# bs_prod.net
KiCad netlist of a schematic drawn in EAGLE
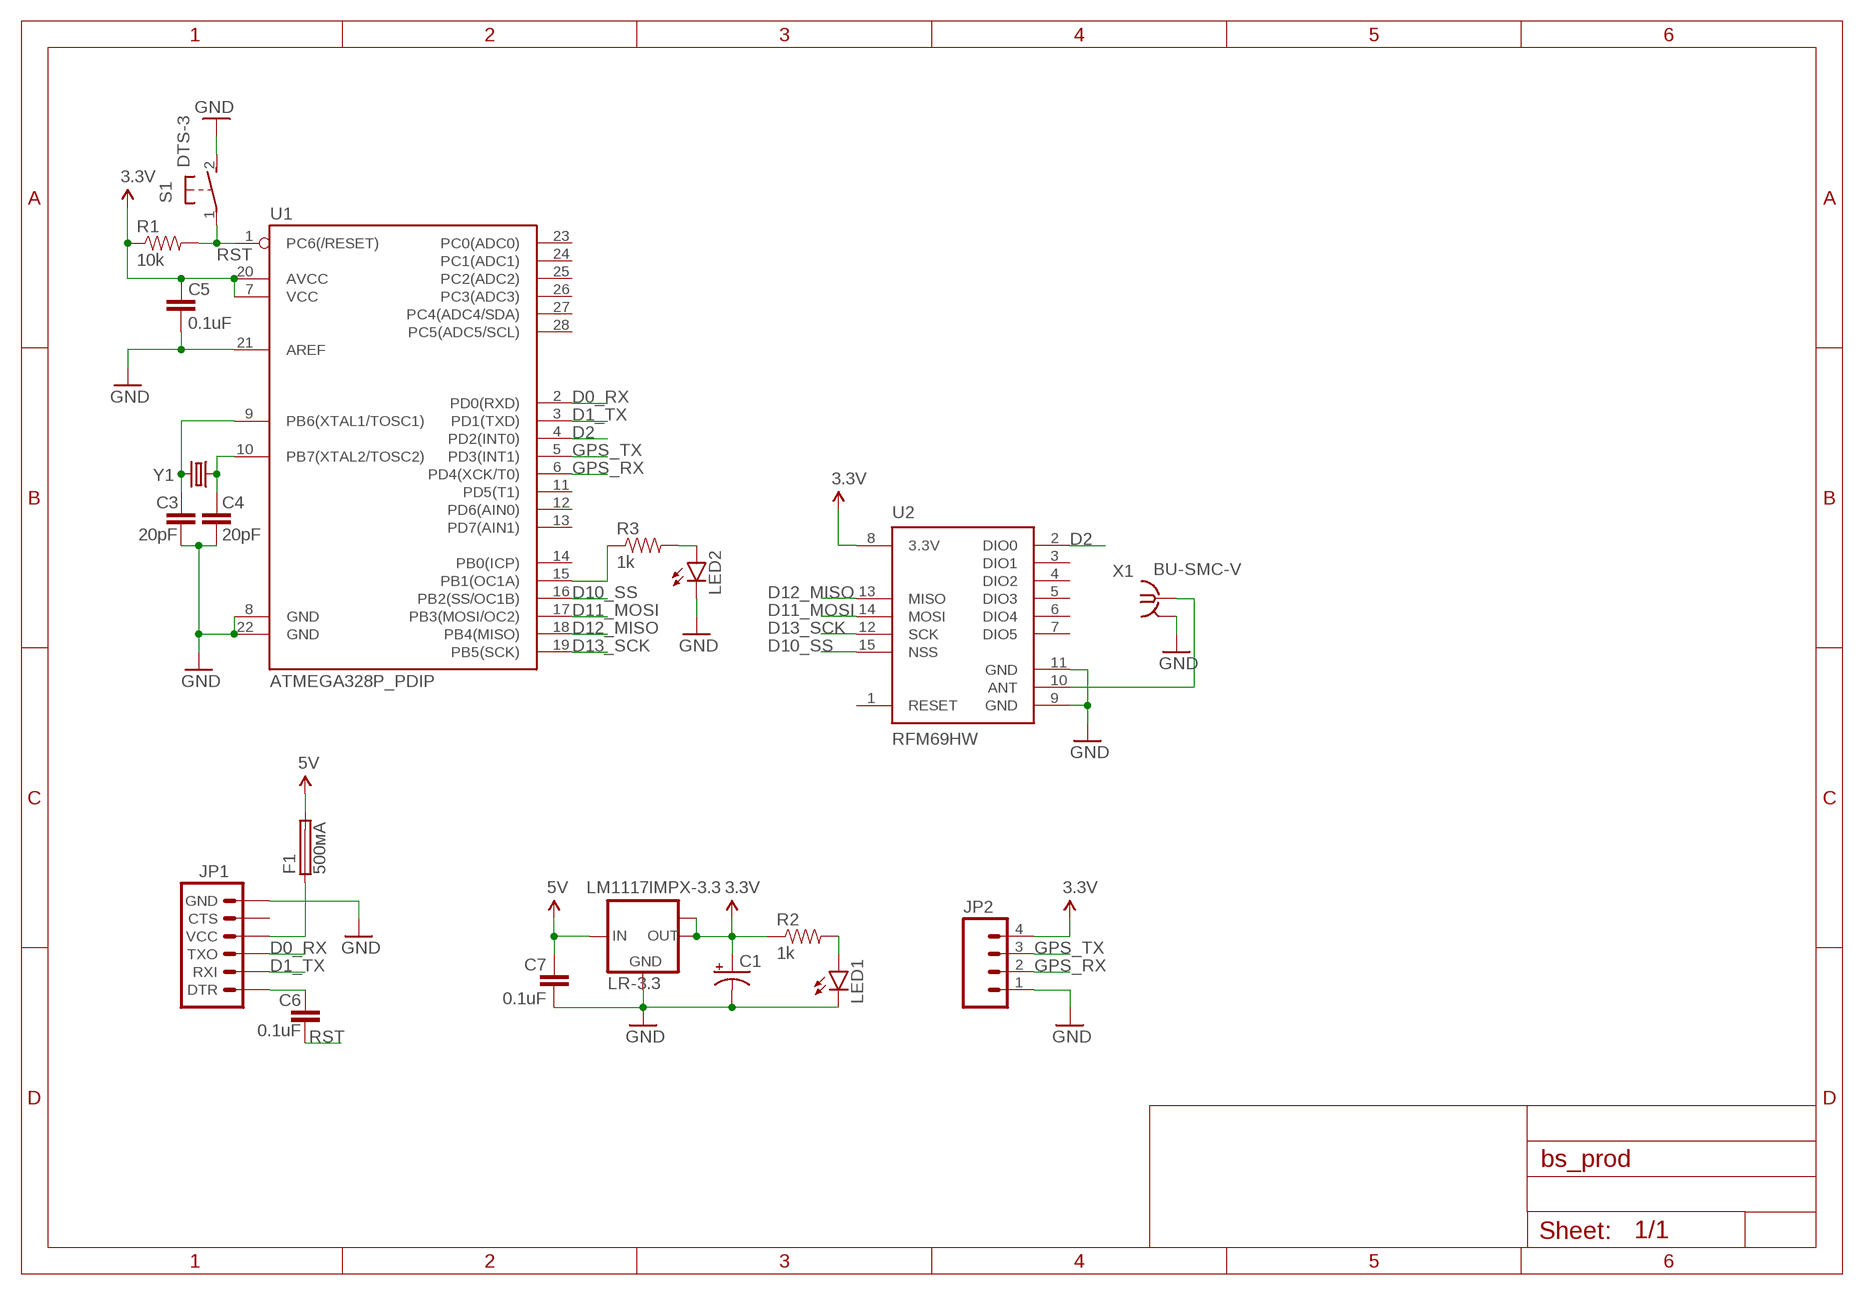
[diagram p0: schematic, sheet 1]

(export (version "E")
  (design (tool "Eeschema 10.0.6"))
  (components
    (comp (ref "C1")
      (value "47UF-50V-20%(ELECT)")
      (footprint "eagle-import:PANASONIC_D")
      (libsource (lib "eagle-import") (part "47UF-50V-20%(ELECT)"))
    )
    (comp (ref "C3")
      (value "20pF")
      (footprint "eagle-import:1206")
      (libsource (lib "eagle-import") (part "CAP1206"))
    )
    (comp (ref "C4")
      (value "20pF")
      (footprint "eagle-import:1206")
      (libsource (lib "eagle-import") (part "CAP1206"))
    )
    (comp (ref "C5")
      (value "0.1uF")
      (footprint "eagle-import:1206")
      (libsource (lib "eagle-import") (part "CAP1206"))
    )
    (comp (ref "C6")
      (value "0.1uF")
      (footprint "eagle-import:1206")
      (libsource (lib "eagle-import") (part "CAP1206"))
    )
    (comp (ref "C7")
      (value "0.1uF")
      (footprint "eagle-import:1206")
      (libsource (lib "eagle-import") (part "CAP1206"))
    )
    (comp (ref "F1")
      (value "500мА")
      (footprint "eagle-import:TE5")
      (libsource (lib "eagle-import") (part "TE5"))
    )
    (comp (ref "JP1")
      (value "ARDUINO_SERIAL_PROGRAMPTH")
      (footprint "eagle-import:1X06")
      (libsource (lib "eagle-import") (part "ARDUINO_SERIAL_PROGRAMPTH"))
    )
    (comp (ref "JP2")
      (value "M04PTH")
      (footprint "eagle-import:1X04")
      (libsource (lib "eagle-import") (part "M04PTH"))
    )
    (comp (ref "LED1")
      (value "LED1206")
      (footprint "eagle-import:LED-1206")
      (libsource (lib "eagle-import") (part "LED1206"))
    )
    (comp (ref "LED2")
      (value "LED1206")
      (footprint "eagle-import:LED-1206")
      (libsource (lib "eagle-import") (part "LED1206"))
    )
    (comp (ref "LR-3.3")
      (value "LM1117IMPX-3.3")
      (footprint "eagle-import:SOT223")
      (libsource (lib "eagle-import") (part "LM1117IMPX-3.3"))
    )
    (comp (ref "R1")
      (value "10k")
      (footprint "eagle-import:1206")
      (libsource (lib "eagle-import") (part "RESISTOR1206"))
    )
    (comp (ref "R2")
      (value "1k")
      (footprint "eagle-import:1206")
      (libsource (lib "eagle-import") (part "RESISTOR1206"))
    )
    (comp (ref "R3")
      (value "1k")
      (footprint "eagle-import:1206")
      (libsource (lib "eagle-import") (part "RESISTOR1206"))
    )
    (comp (ref "S1")
      (value "DTS-3")
      (footprint "eagle-import:DTS-3")
      (libsource (lib "eagle-import") (part "DTS-3"))
    )
    (comp (ref "U1")
      (value "ATMEGA328P_PDIP")
      (footprint "eagle-import:DIL28-3")
      (libsource (lib "eagle-import") (part "ATMEGA328P_PDIP"))
    )
    (comp (ref "U2")
      (value "RFM69HW")
      (footprint "eagle-import:RFM69W-XXXS2")
      (libsource (lib "eagle-import") (part "RFM69HW"))
    )
    (comp (ref "X1")
      (value "BU-SMC-V")
      (footprint "eagle-import:BU-SMC-V")
      (libsource (lib "eagle-import") (part "BU-SMC-V"))
    )
    (comp (ref "Y1")
      (value "CRYSTALSMD")
      (footprint "eagle-import:HC49UP")
      (libsource (lib "eagle-import") (part "CRYSTALSMD"))
    )
  )
  (nets
    (net (code "1") (name "/D0_RX") (class "Default")
      (node (ref "JP1") (pin "3") (pinfunction "TXO_3") (pintype "passive"))
      (node (ref "U1") (pin "2") (pinfunction "PD0(RXD)_2") (pintype "bidirectional"))
    )
    (net (code "2") (name "/D1_TX") (class "Default")
      (node (ref "JP1") (pin "2") (pinfunction "RXI_2") (pintype "passive"))
      (node (ref "U1") (pin "3") (pinfunction "PD1(TXD)_3") (pintype "bidirectional"))
    )
    (net (code "3") (name "/D2") (class "Default")
      (node (ref "U1") (pin "4") (pinfunction "PD2(INT0)_4") (pintype "bidirectional"))
      (node (ref "U2") (pin "2") (pinfunction "DIO0_2") (pintype "bidirectional"))
    )
    (net (code "4") (name "/D10_SS") (class "Default")
      (node (ref "U1") (pin "16") (pinfunction "PB2(SS/OC1B)_16") (pintype "bidirectional"))
      (node (ref "U2") (pin "15") (pinfunction "NSS_15") (pintype "input"))
    )
    (net (code "5") (name "/D11_MOSI") (class "Default")
      (node (ref "U1") (pin "17") (pinfunction "PB3(MOSI/OC2)_17") (pintype "bidirectional"))
      (node (ref "U2") (pin "14") (pinfunction "MOSI_14") (pintype "input"))
    )
    (net (code "6") (name "/D12_MISO") (class "Default")
      (node (ref "U1") (pin "18") (pinfunction "PB4(MISO)_18") (pintype "bidirectional"))
      (node (ref "U2") (pin "13") (pinfunction "MISO_13") (pintype "bidirectional"))
    )
    (net (code "7") (name "/D13_SCK") (class "Default")
      (node (ref "U1") (pin "19") (pinfunction "PB5(SCK)_19") (pintype "bidirectional"))
      (node (ref "U2") (pin "12") (pinfunction "SCK_12") (pintype "input"))
    )
    (net (code "8") (name "/GPS_RX") (class "Default")
      (node (ref "JP2") (pin "2") (pinfunction "2_2") (pintype "passive"))
      (node (ref "U1") (pin "6") (pinfunction "PD4(XCK/T0)_6") (pintype "bidirectional"))
    )
    (net (code "9") (name "/GPS_TX") (class "Default")
      (node (ref "JP2") (pin "3") (pinfunction "3_3") (pintype "passive"))
      (node (ref "U1") (pin "5") (pinfunction "PD3(INT1)_5") (pintype "bidirectional"))
    )
    (net (code "10") (name "/RST") (class "Default")
      (node (ref "C6") (pin "2") (pinfunction "2_2") (pintype "passive"))
      (node (ref "R1") (pin "2") (pinfunction "2_2") (pintype "passive"))
      (node (ref "S1") (pin "1") (pinfunction "1_1") (pintype "passive"))
      (node (ref "U1") (pin "1") (pinfunction "PC6(/RESET)_1") (pintype "bidirectional"))
    )
    (net (code "11") (name "3.3V") (class "Default")
      (node (ref "C1") (pin "+") (pinfunction "+_+") (pintype "passive"))
      (node (ref "C5") (pin "1") (pinfunction "1_1") (pintype "passive"))
      (node (ref "JP2") (pin "4") (pinfunction "4_4") (pintype "passive"))
      (node (ref "LR-3.3") (pin "2") (pinfunction "OUT_2") (pintype "passive"))
      (node (ref "LR-3.3") (pin "TAB") (pinfunction "OUT1_TAB") (pintype "passive"))
      (node (ref "R1") (pin "1") (pinfunction "1_1") (pintype "passive"))
      (node (ref "R2") (pin "1") (pinfunction "1_1") (pintype "passive"))
      (node (ref "U1") (pin "20") (pinfunction "AVCC_20") (pintype "bidirectional"))
      (node (ref "U1") (pin "7") (pinfunction "VCC_7") (pintype "bidirectional"))
      (node (ref "U2") (pin "8") (pinfunction "3.3V_8") (pintype "power_in"))
    )
    (net (code "12") (name "5V") (class "Default")
      (node (ref "C7") (pin "1") (pinfunction "1_1") (pintype "passive"))
      (node (ref "F1") (pin "2") (pinfunction "2_2") (pintype "passive"))
      (node (ref "LR-3.3") (pin "3") (pinfunction "IN_3") (pintype "input"))
    )
    (net (code "13") (name "GND") (class "Default")
      (node (ref "C1") (pin "-") (pinfunction "-_-") (pintype "passive"))
      (node (ref "C3") (pin "2") (pinfunction "2_2") (pintype "passive"))
      (node (ref "C4") (pin "2") (pinfunction "2_2") (pintype "passive"))
      (node (ref "C5") (pin "2") (pinfunction "2_2") (pintype "passive"))
      (node (ref "C7") (pin "2") (pinfunction "2_2") (pintype "passive"))
      (node (ref "JP1") (pin "6") (pinfunction "GND_6") (pintype "passive"))
      (node (ref "JP2") (pin "1") (pinfunction "1_1") (pintype "passive"))
      (node (ref "LED1") (pin "C") (pinfunction "C_C") (pintype "passive"))
      (node (ref "LED2") (pin "C") (pinfunction "C_C") (pintype "passive"))
      (node (ref "LR-3.3") (pin "1") (pinfunction "GND_1") (pintype "input"))
      (node (ref "S1") (pin "2") (pinfunction "2_2") (pintype "passive"))
      (node (ref "U1") (pin "21") (pinfunction "AREF_21") (pintype "bidirectional"))
      (node (ref "U1") (pin "22") (pinfunction "GND_22") (pintype "bidirectional"))
      (node (ref "U1") (pin "8") (pinfunction "GND_8") (pintype "bidirectional"))
      (node (ref "U2") (pin "11") (pinfunction "GND_11") (pintype "power_in"))
      (node (ref "U2") (pin "9") (pinfunction "GND_9") (pintype "power_in"))
      (node (ref "X1") (pin "2") (pinfunction "2_2") (pintype "passive"))
      (node (ref "X1") (pin "3") (pinfunction "2_3") (pintype "passive"))
      (node (ref "X1") (pin "4") (pinfunction "2_4") (pintype "passive"))
      (node (ref "X1") (pin "5") (pinfunction "2_5") (pintype "passive"))
    )
    (net (code "14") (name "Net-(JP1-DTR)") (class "Default")
      (node (ref "C6") (pin "1") (pinfunction "1_1") (pintype "passive"))
      (node (ref "JP1") (pin "1") (pinfunction "DTR_1") (pintype "passive"))
    )
    (net (code "15") (name "Net-(JP1-VCC)") (class "Default")
      (node (ref "F1") (pin "1") (pinfunction "1_1") (pintype "passive"))
      (node (ref "JP1") (pin "4") (pinfunction "VCC_4") (pintype "passive"))
    )
    (net (code "16") (name "Net-(LED1-PadA)") (class "Default")
      (node (ref "LED1") (pin "A") (pinfunction "A_A") (pintype "passive"))
      (node (ref "R2") (pin "2") (pinfunction "2_2") (pintype "passive"))
    )
    (net (code "17") (name "Net-(LED2-PadA)") (class "Default")
      (node (ref "LED2") (pin "A") (pinfunction "A_A") (pintype "passive"))
      (node (ref "R3") (pin "2") (pinfunction "2_2") (pintype "passive"))
    )
    (net (code "18") (name "Net-(U1-PB1(OC1A))") (class "Default")
      (node (ref "R3") (pin "1") (pinfunction "1_1") (pintype "passive"))
      (node (ref "U1") (pin "15") (pinfunction "PB1(OC1A)_15") (pintype "bidirectional"))
    )
    (net (code "19") (name "Net-(U1-PB6(XTAL1{slash}TOSC1))") (class "Default")
      (node (ref "C3") (pin "1") (pinfunction "1_1") (pintype "passive"))
      (node (ref "U1") (pin "9") (pinfunction "PB6(XTAL1/TOSC1)_9") (pintype "bidirectional"))
      (node (ref "Y1") (pin "2") (pinfunction "2_2") (pintype "passive"))
    )
    (net (code "20") (name "Net-(U1-PB7(XTAL2{slash}TOSC2))") (class "Default")
      (node (ref "C4") (pin "1") (pinfunction "1_1") (pintype "passive"))
      (node (ref "U1") (pin "10") (pinfunction "PB7(XTAL2/TOSC2)_10") (pintype "bidirectional"))
      (node (ref "Y1") (pin "1") (pinfunction "1_1") (pintype "passive"))
    )
    (net (code "21") (name "Net-(U2-ANT)") (class "Default")
      (node (ref "U2") (pin "10") (pinfunction "ANT_10") (pintype "passive"))
      (node (ref "X1") (pin "1") (pinfunction "1_1") (pintype "passive"))
    )
    (net (code "22") (name "unconnected-(JP1-CTS-Pad5)") (class "Default")
      (node (ref "JP1") (pin "5") (pinfunction "CTS_5") (pintype "passive"))
    )
    (net (code "23") (name "unconnected-(U1-PB0(ICP)-Pad14)") (class "Default")
      (node (ref "U1") (pin "14") (pinfunction "PB0(ICP)_14") (pintype "bidirectional"))
    )
    (net (code "24") (name "unconnected-(U1-PC0(ADC0)-Pad23)") (class "Default")
      (node (ref "U1") (pin "23") (pinfunction "PC0(ADC0)_23") (pintype "bidirectional"))
    )
    (net (code "25") (name "unconnected-(U1-PC1(ADC1)-Pad24)") (class "Default")
      (node (ref "U1") (pin "24") (pinfunction "PC1(ADC1)_24") (pintype "bidirectional"))
    )
    (net (code "26") (name "unconnected-(U1-PC2(ADC2)-Pad25)") (class "Default")
      (node (ref "U1") (pin "25") (pinfunction "PC2(ADC2)_25") (pintype "bidirectional"))
    )
    (net (code "27") (name "unconnected-(U1-PC3(ADC3)-Pad26)") (class "Default")
      (node (ref "U1") (pin "26") (pinfunction "PC3(ADC3)_26") (pintype "bidirectional"))
    )
    (net (code "28") (name "unconnected-(U1-PC4(ADC4{slash}SDA)-Pad27)") (class "Default")
      (node (ref "U1") (pin "27") (pinfunction "PC4(ADC4/SDA)_27") (pintype "bidirectional"))
    )
    (net (code "29") (name "unconnected-(U1-PC5(ADC5{slash}SCL)-Pad28)") (class "Default")
      (node (ref "U1") (pin "28") (pinfunction "PC5(ADC5/SCL)_28") (pintype "bidirectional"))
    )
    (net (code "30") (name "unconnected-(U1-PD5(T1)-Pad11)") (class "Default")
      (node (ref "U1") (pin "11") (pinfunction "PD5(T1)_11") (pintype "bidirectional"))
    )
    (net (code "31") (name "unconnected-(U1-PD6(AIN0)-Pad12)") (class "Default")
      (node (ref "U1") (pin "12") (pinfunction "PD6(AIN0)_12") (pintype "bidirectional"))
    )
    (net (code "32") (name "unconnected-(U1-PD7(AIN1)-Pad13)") (class "Default")
      (node (ref "U1") (pin "13") (pinfunction "PD7(AIN1)_13") (pintype "bidirectional"))
    )
    (net (code "33") (name "unconnected-(U2-DIO1-Pad3)") (class "Default")
      (node (ref "U2") (pin "3") (pinfunction "DIO1_3") (pintype "bidirectional"))
    )
    (net (code "34") (name "unconnected-(U2-DIO2-Pad4)") (class "Default")
      (node (ref "U2") (pin "4") (pinfunction "DIO2_4") (pintype "bidirectional"))
    )
    (net (code "35") (name "unconnected-(U2-DIO3-Pad5)") (class "Default")
      (node (ref "U2") (pin "5") (pinfunction "DIO3_5") (pintype "bidirectional"))
    )
    (net (code "36") (name "unconnected-(U2-DIO4-Pad6)") (class "Default")
      (node (ref "U2") (pin "6") (pinfunction "DIO4_6") (pintype "bidirectional"))
    )
    (net (code "37") (name "unconnected-(U2-DIO5-Pad7)") (class "Default")
      (node (ref "U2") (pin "7") (pinfunction "DIO5_7") (pintype "bidirectional"))
    )
    (net (code "38") (name "unconnected-(U2-RESET-Pad1)") (class "Default")
      (node (ref "U2") (pin "1") (pinfunction "RESET_1") (pintype "input"))
    )
  )
)
